# L9741.net
KiCad netlist of a schematic drawn in Altium Designer
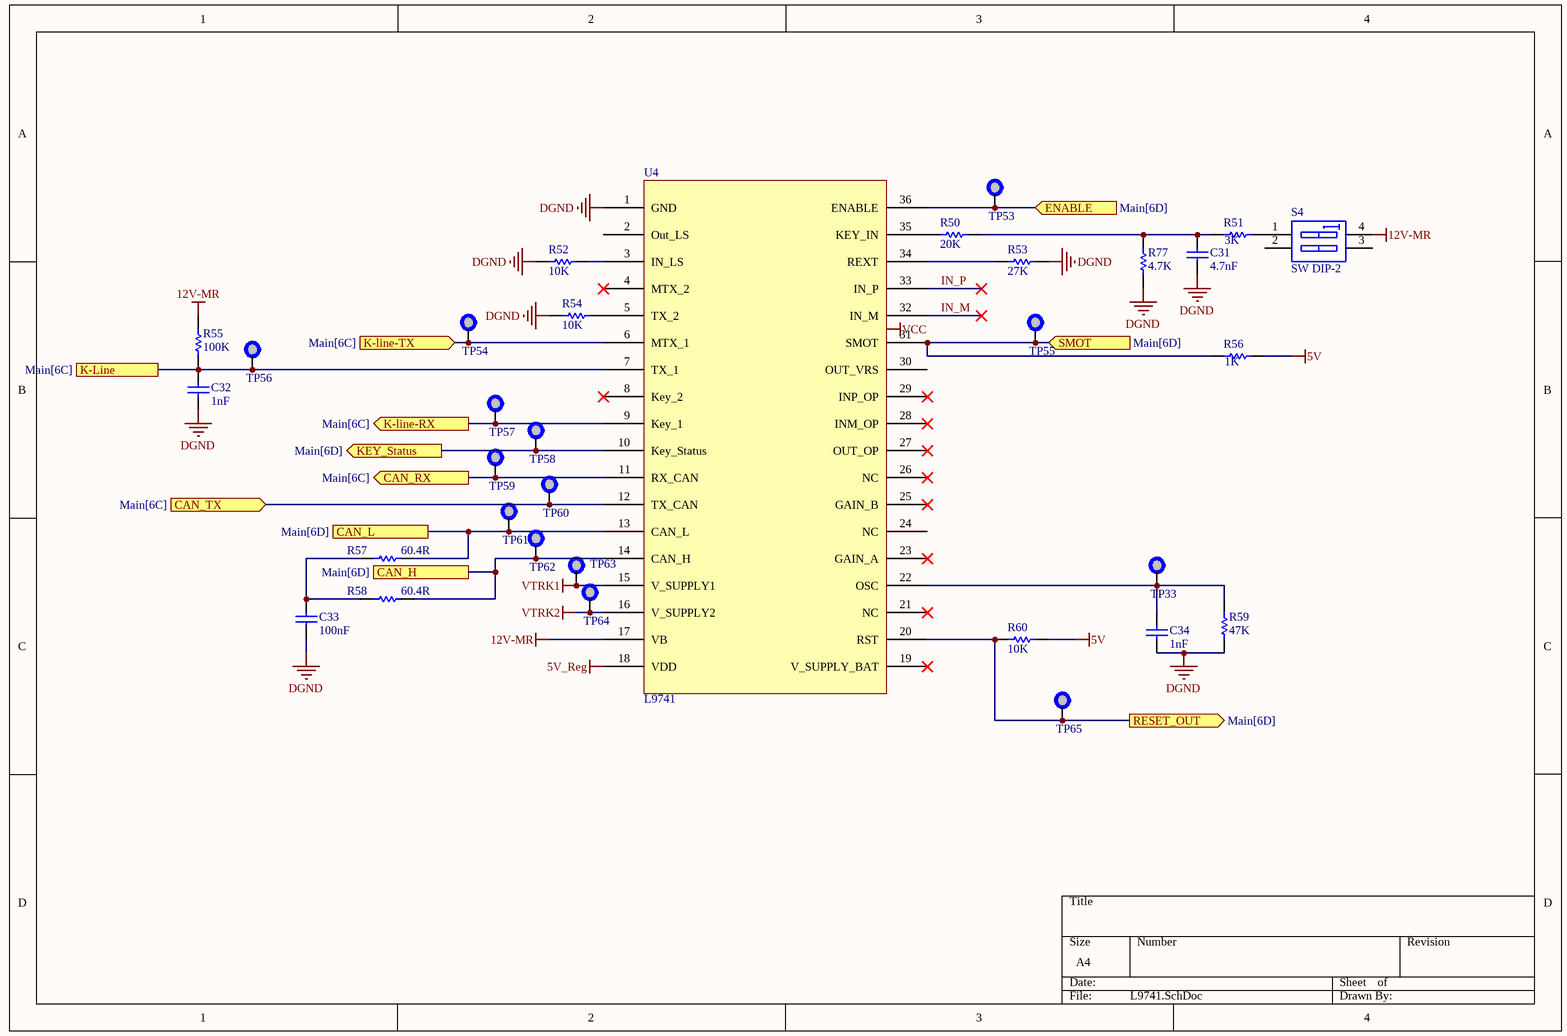
[diagram p0: L9741.SchDoc]

(export (version "E")
  (design (tool "Eeschema 10.0.6"))
  (components
    (comp (ref "C31")
      (value "4.7nF")
      (footprint "0805C")
      (description "Capacitor")
      (fields (field (name "Comment") "CGA5L1X7R1H106K160AC") (field (name "PUBLISHER") "Altium Limited"))
      (libsource (lib "Miscellaneous Devices") (part "Cap"))
    )
    (comp (ref "C32")
      (value "1nF")
      (footprint "0603C")
      (description "Capacitor")
      (fields (field (name "Comment") "CGA3E2X7R1H104K080AA") (field (name "PUBLISHER") "Altium Limited"))
      (libsource (lib "Miscellaneous Devices") (part "Cap"))
    )
    (comp (ref "C33")
      (value "100nF")
      (footprint "0603C")
      (description "Capacitor")
      (fields (field (name "Comment") "CGA3E2X7R1H104K080AA") (field (name "PUBLISHER") "Altium Limited"))
      (libsource (lib "Miscellaneous Devices") (part "Cap"))
    )
    (comp (ref "C34")
      (value "1nF")
      (footprint "0805C")
      (description "Capacitor")
      (fields (field (name "Comment") "CGA5L1X7R1H106K160AC") (field (name "PUBLISHER") "Altium Limited"))
      (libsource (lib "Miscellaneous Devices") (part "Cap"))
    )
    (comp (ref "R50")
      (value "20K")
      (footprint "0805")
      (description "Resistor")
      (fields (field (name "Comment") "Res1") (field (name "PUBLISHER") "Altium Limited"))
      (libsource (lib "Miscellaneous Devices") (part "Res1"))
    )
    (comp (ref "R51")
      (value "3K")
      (footprint "0805")
      (description "Resistor")
      (fields (field (name "Comment") "Res1") (field (name "PUBLISHER") "Altium Limited"))
      (libsource (lib "Miscellaneous Devices") (part "Res1"))
    )
    (comp (ref "R52")
      (value "10K")
      (footprint "0805")
      (description "Resistor")
      (fields (field (name "Comment") "Res1") (field (name "PUBLISHER") "Altium Limited"))
      (libsource (lib "Miscellaneous Devices") (part "Res1"))
    )
    (comp (ref "R53")
      (value "27K")
      (footprint "0805")
      (description "Resistor")
      (fields (field (name "Comment") "Res1") (field (name "PUBLISHER") "Altium Limited"))
      (libsource (lib "Miscellaneous Devices") (part "Res1"))
    )
    (comp (ref "R54")
      (value "10K")
      (footprint "0805")
      (description "Resistor")
      (fields (field (name "Comment") "Res1") (field (name "PUBLISHER") "Altium Limited"))
      (libsource (lib "Miscellaneous Devices") (part "Res1"))
    )
    (comp (ref "R55")
      (value "100K")
      (footprint "0805")
      (description "Resistor")
      (fields (field (name "Comment") "Res1") (field (name "PUBLISHER") "Altium Limited"))
      (libsource (lib "Miscellaneous Devices") (part "Res1"))
    )
    (comp (ref "R56")
      (value "1K")
      (footprint "0805")
      (description "Resistor")
      (fields (field (name "Comment") "Res1") (field (name "PUBLISHER") "Altium Limited"))
      (libsource (lib "Miscellaneous Devices") (part "Res1"))
    )
    (comp (ref "R57")
      (value "60.4R")
      (footprint "1206")
      (description "Resistor")
      (fields (field (name "Comment") "Res1") (field (name "PUBLISHER") "Altium Limited"))
      (libsource (lib "Miscellaneous Devices") (part "Res1"))
    )
    (comp (ref "R58")
      (value "60.4R")
      (footprint "1206")
      (description "Resistor")
      (fields (field (name "Comment") "Res1") (field (name "PUBLISHER") "Altium Limited"))
      (libsource (lib "Miscellaneous Devices") (part "Res1"))
    )
    (comp (ref "R59")
      (value "47K")
      (footprint "0805")
      (description "Resistor")
      (fields (field (name "Comment") "Res1") (field (name "PUBLISHER") "Altium Limited"))
      (libsource (lib "Miscellaneous Devices") (part "Res1"))
    )
    (comp (ref "R60")
      (value "10K")
      (footprint "0805")
      (description "Resistor")
      (fields (field (name "Comment") "Res1") (field (name "PUBLISHER") "Altium Limited"))
      (libsource (lib "Miscellaneous Devices") (part "Res1"))
    )
    (comp (ref "R77")
      (value "4.7K")
      (footprint "0805")
      (description "Resistor")
      (fields (field (name "Comment") "Res1") (field (name "PUBLISHER") "Altium Limited"))
      (libsource (lib "Miscellaneous Devices") (part "Res1"))
    )
    (comp (ref "S4")
      (value "SW DIP-2")
      (footprint "DIP-4")
      (description "DIP Switch, 2 Position, SPST")
      (fields (field (name "PUBLISHER") "Altium Limited"))
      (libsource (lib "Miscellaneous Devices") (part "SW DIP-2"))
    )
    (comp (ref "TP33") (value "TestPoint") (footprint "TP") (libsource (lib "SchlibV0.1") (part "TestPoint")))
    (comp (ref "TP53") (value "TestPoint") (footprint "TP") (libsource (lib "SchlibV0.1") (part "TestPoint")))
    (comp (ref "TP54") (value "TestPoint") (footprint "TP") (libsource (lib "SchlibV0.1") (part "TestPoint")))
    (comp (ref "TP55") (value "TestPoint") (footprint "TP") (libsource (lib "SchlibV0.1") (part "TestPoint")))
    (comp (ref "TP56") (value "TestPoint") (footprint "TP") (libsource (lib "SchlibV0.1") (part "TestPoint")))
    (comp (ref "TP57") (value "TestPoint") (footprint "TP") (libsource (lib "SchlibV0.1") (part "TestPoint")))
    (comp (ref "TP58") (value "TestPoint") (footprint "TP") (libsource (lib "SchlibV0.1") (part "TestPoint")))
    (comp (ref "TP59") (value "TestPoint") (footprint "TP") (libsource (lib "SchlibV0.1") (part "TestPoint")))
    (comp (ref "TP60") (value "TestPoint") (footprint "TP") (libsource (lib "SchlibV0.1") (part "TestPoint")))
    (comp (ref "TP61") (value "TestPoint") (footprint "TP") (libsource (lib "SchlibV0.1") (part "TestPoint")))
    (comp (ref "TP62") (value "TestPoint") (footprint "TP") (libsource (lib "SchlibV0.1") (part "TestPoint")))
    (comp (ref "TP63") (value "TestPoint") (footprint "TP") (libsource (lib "SchlibV0.1") (part "TestPoint")))
    (comp (ref "TP64") (value "TestPoint") (footprint "TP") (libsource (lib "SchlibV0.1") (part "TestPoint")))
    (comp (ref "TP65") (value "TestPoint") (footprint "TP") (libsource (lib "SchlibV0.1") (part "TestPoint")))
    (comp (ref "U4") (value "L9741") (footprint "L9741") (libsource (lib "SchlibV0.1") (part "L9741")))
  )
  (nets
    (net (code "1") (name "/CAN_H") (class "Default")
      (node (ref "R58") (pin "2") (pinfunction "2_2") (pintype "passive"))
      (node (ref "TP62") (pin "1") (pintype "passive"))
      (node (ref "U4") (pin "14") (pinfunction "CAN_H_14") (pintype "passive"))
    )
    (net (code "2") (name "/CAN_L") (class "Default")
      (node (ref "R57") (pin "2") (pinfunction "2_2") (pintype "passive"))
      (node (ref "TP61") (pin "1") (pintype "passive"))
      (node (ref "U4") (pin "13") (pinfunction "CAN_L_13") (pintype "passive"))
    )
    (net (code "3") (name "/CAN_RX") (class "Default")
      (node (ref "TP59") (pin "1") (pintype "passive"))
      (node (ref "U4") (pin "11") (pinfunction "RX_CAN_11") (pintype "passive"))
    )
    (net (code "4") (name "/CAN_TX") (class "Default")
      (node (ref "TP60") (pin "1") (pintype "passive"))
      (node (ref "U4") (pin "12") (pinfunction "TX_CAN_12") (pintype "passive"))
    )
    (net (code "5") (name "/ENABLE") (class "Default")
      (node (ref "TP53") (pin "1") (pintype "passive"))
      (node (ref "U4") (pin "36") (pinfunction "ENABLE_36") (pintype "passive"))
    )
    (net (code "6") (name "/IN_M") (class "Default")
      (node (ref "U4") (pin "32") (pinfunction "IN_M_32") (pintype "passive+no_connect"))
    )
    (net (code "7") (name "/IN_P") (class "Default")
      (node (ref "U4") (pin "33") (pinfunction "IN_P_33") (pintype "passive+no_connect"))
    )
    (net (code "8") (name "/K-Line") (class "Default")
      (node (ref "C32") (pin "1") (pinfunction "1_1") (pintype "passive"))
      (node (ref "R55") (pin "2") (pinfunction "2_2") (pintype "passive"))
      (node (ref "TP56") (pin "1") (pintype "passive"))
      (node (ref "U4") (pin "7") (pinfunction "TX_1_7") (pintype "passive"))
    )
    (net (code "9") (name "/K-line-RX") (class "Default")
      (node (ref "TP57") (pin "1") (pintype "passive"))
      (node (ref "U4") (pin "9") (pinfunction "Key_1_9") (pintype "passive"))
    )
    (net (code "10") (name "/K-line-TX") (class "Default")
      (node (ref "TP54") (pin "1") (pintype "passive"))
      (node (ref "U4") (pin "6") (pinfunction "MTX_1_6") (pintype "passive"))
    )
    (net (code "11") (name "/KEY_Status") (class "Default")
      (node (ref "TP58") (pin "1") (pintype "passive"))
      (node (ref "U4") (pin "10") (pinfunction "Key_Status_10") (pintype "passive"))
    )
    (net (code "12") (name "/RESET_OUT") (class "Default")
      (node (ref "R60") (pin "2") (pinfunction "2_2") (pintype "passive"))
      (node (ref "TP65") (pin "1") (pintype "passive"))
      (node (ref "U4") (pin "20") (pinfunction "RST_20") (pintype "passive"))
    )
    (net (code "13") (name "/SMOT") (class "Default")
      (node (ref "R56") (pin "1") (pinfunction "1_1") (pintype "passive"))
      (node (ref "TP55") (pin "1") (pintype "passive"))
      (node (ref "U4") (pin "31") (pinfunction "SMOT_31") (pintype "passive"))
    )
    (net (code "14") (name "5V") (class "Default")
      (node (ref "R56") (pin "2") (pinfunction "2_2") (pintype "passive"))
      (node (ref "R60") (pin "1") (pinfunction "1_1") (pintype "passive"))
    )
    (net (code "15") (name "5V_Reg") (class "Default")
      (node (ref "U4") (pin "18") (pinfunction "VDD_18") (pintype "passive"))
    )
    (net (code "16") (name "12V-MR") (class "Default")
      (node (ref "R55") (pin "1") (pinfunction "1_1") (pintype "passive"))
      (node (ref "S4") (pin "4") (pinfunction "B1_4") (pintype "passive"))
      (node (ref "U4") (pin "17") (pinfunction "VB_17") (pintype "passive"))
    )
    (net (code "17") (name "DGND") (class "Default")
      (node (ref "C31") (pin "1") (pinfunction "1_1") (pintype "passive"))
      (node (ref "C32") (pin "2") (pinfunction "2_2") (pintype "passive"))
      (node (ref "C33") (pin "2") (pinfunction "2_2") (pintype "passive"))
      (node (ref "C34") (pin "2") (pinfunction "2_2") (pintype "passive"))
      (node (ref "R52") (pin "2") (pinfunction "2_2") (pintype "passive"))
      (node (ref "R53") (pin "1") (pinfunction "1_1") (pintype "passive"))
      (node (ref "R54") (pin "2") (pinfunction "2_2") (pintype "passive"))
      (node (ref "R59") (pin "2") (pinfunction "2_2") (pintype "passive"))
      (node (ref "R77") (pin "2") (pinfunction "2_2") (pintype "passive"))
      (node (ref "U4") (pin "1") (pinfunction "GND_1") (pintype "passive"))
    )
    (net (code "18") (name "Net-(C31-Pad2)") (class "Default")
      (node (ref "C31") (pin "2") (pinfunction "2_2") (pintype "passive"))
      (node (ref "R50") (pin "1") (pinfunction "1_1") (pintype "passive"))
      (node (ref "R51") (pin "1") (pinfunction "1_1") (pintype "passive"))
      (node (ref "R77") (pin "1") (pinfunction "1_1") (pintype "passive"))
    )
    (net (code "19") (name "Net-(C33-Pad1)") (class "Default")
      (node (ref "C33") (pin "1") (pinfunction "1_1") (pintype "passive"))
      (node (ref "R57") (pin "1") (pinfunction "1_1") (pintype "passive"))
      (node (ref "R58") (pin "1") (pinfunction "1_1") (pintype "passive"))
    )
    (net (code "20") (name "Net-(S4-A1)") (class "Default")
      (node (ref "R51") (pin "2") (pinfunction "2_2") (pintype "passive"))
      (node (ref "S4") (pin "1") (pinfunction "A1_1") (pintype "passive"))
    )
    (net (code "21") (name "Net-(U4-IN_LS)") (class "Default")
      (node (ref "R52") (pin "1") (pinfunction "1_1") (pintype "passive"))
      (node (ref "U4") (pin "3") (pinfunction "IN_LS_3") (pintype "passive"))
    )
    (net (code "22") (name "Net-(U4-KEY_IN)") (class "Default")
      (node (ref "R50") (pin "2") (pinfunction "2_2") (pintype "passive"))
      (node (ref "U4") (pin "35") (pinfunction "KEY_IN_35") (pintype "passive"))
    )
    (net (code "23") (name "Net-(U4-OSC)") (class "Default")
      (node (ref "C34") (pin "1") (pinfunction "1_1") (pintype "passive"))
      (node (ref "R59") (pin "1") (pinfunction "1_1") (pintype "passive"))
      (node (ref "TP33") (pin "1") (pintype "passive"))
      (node (ref "U4") (pin "22") (pinfunction "OSC_22") (pintype "passive"))
    )
    (net (code "24") (name "Net-(U4-REXT)") (class "Default")
      (node (ref "R53") (pin "2") (pinfunction "2_2") (pintype "passive"))
      (node (ref "U4") (pin "34") (pinfunction "REXT_34") (pintype "passive"))
    )
    (net (code "25") (name "Net-(U4-TX_2)") (class "Default")
      (node (ref "R54") (pin "1") (pinfunction "1_1") (pintype "passive"))
      (node (ref "U4") (pin "5") (pinfunction "TX_2_5") (pintype "passive"))
    )
    (net (code "27") (name "VTRK1") (class "Default")
      (node (ref "TP63") (pin "1") (pintype "passive"))
      (node (ref "U4") (pin "15") (pinfunction "V_SUPPLY1_15") (pintype "passive"))
    )
    (net (code "28") (name "VTRK2") (class "Default")
      (node (ref "TP64") (pin "1") (pintype "passive"))
      (node (ref "U4") (pin "16") (pinfunction "V_SUPPLY2_16") (pintype "passive"))
    )
    (net (code "29") (name "unconnected-(S4-A2-Pad2)") (class "Default")
      (node (ref "S4") (pin "2") (pinfunction "A2_2") (pintype "passive"))
    )
    (net (code "30") (name "unconnected-(S4-B2-Pad3)") (class "Default")
      (node (ref "S4") (pin "3") (pinfunction "B2_3") (pintype "passive"))
    )
    (net (code "31") (name "unconnected-(U4-GAIN_A-Pad23)") (class "Default")
      (node (ref "U4") (pin "23") (pinfunction "GAIN_A_23") (pintype "passive+no_connect"))
    )
    (net (code "32") (name "unconnected-(U4-GAIN_B-Pad25)") (class "Default")
      (node (ref "U4") (pin "25") (pinfunction "GAIN_B_25") (pintype "passive+no_connect"))
    )
    (net (code "33") (name "unconnected-(U4-INM_OP-Pad28)") (class "Default")
      (node (ref "U4") (pin "28") (pinfunction "INM_OP_28") (pintype "passive+no_connect"))
    )
    (net (code "34") (name "unconnected-(U4-INP_OP-Pad29)") (class "Default")
      (node (ref "U4") (pin "29") (pinfunction "INP_OP_29") (pintype "passive+no_connect"))
    )
    (net (code "35") (name "unconnected-(U4-Key_2-Pad8)") (class "Default")
      (node (ref "U4") (pin "8") (pinfunction "Key_2_8") (pintype "passive+no_connect"))
    )
    (net (code "36") (name "unconnected-(U4-MTX_2-Pad4)") (class "Default")
      (node (ref "U4") (pin "4") (pinfunction "MTX_2_4") (pintype "passive+no_connect"))
    )
    (net (code "37") (name "unconnected-(U4-NC-Pad21)") (class "Default")
      (node (ref "U4") (pin "21") (pinfunction "NC_21") (pintype "passive+no_connect"))
    )
    (net (code "38") (name "unconnected-(U4-NC-Pad24)") (class "Default")
      (node (ref "U4") (pin "24") (pinfunction "NC_24") (pintype "passive"))
    )
    (net (code "39") (name "unconnected-(U4-NC-Pad26)") (class "Default")
      (node (ref "U4") (pin "26") (pinfunction "NC_26") (pintype "passive+no_connect"))
    )
    (net (code "40") (name "unconnected-(U4-OUT_OP-Pad27)") (class "Default")
      (node (ref "U4") (pin "27") (pinfunction "OUT_OP_27") (pintype "passive+no_connect"))
    )
    (net (code "41") (name "unconnected-(U4-OUT_VRS-Pad30)") (class "Default")
      (node (ref "U4") (pin "30") (pinfunction "OUT_VRS_30") (pintype "passive"))
    )
    (net (code "42") (name "unconnected-(U4-Out_LS-Pad2)") (class "Default")
      (node (ref "U4") (pin "2") (pinfunction "Out_LS_2") (pintype "passive"))
    )
    (net (code "43") (name "unconnected-(U4-V_SUPPLY_BAT-Pad19)") (class "Default")
      (node (ref "U4") (pin "19") (pinfunction "V_SUPPLY_BAT_19") (pintype "passive+no_connect"))
    )
  )
)
